# MainBoard_Eagle7.net
KiCad netlist of a schematic drawn in EAGLE
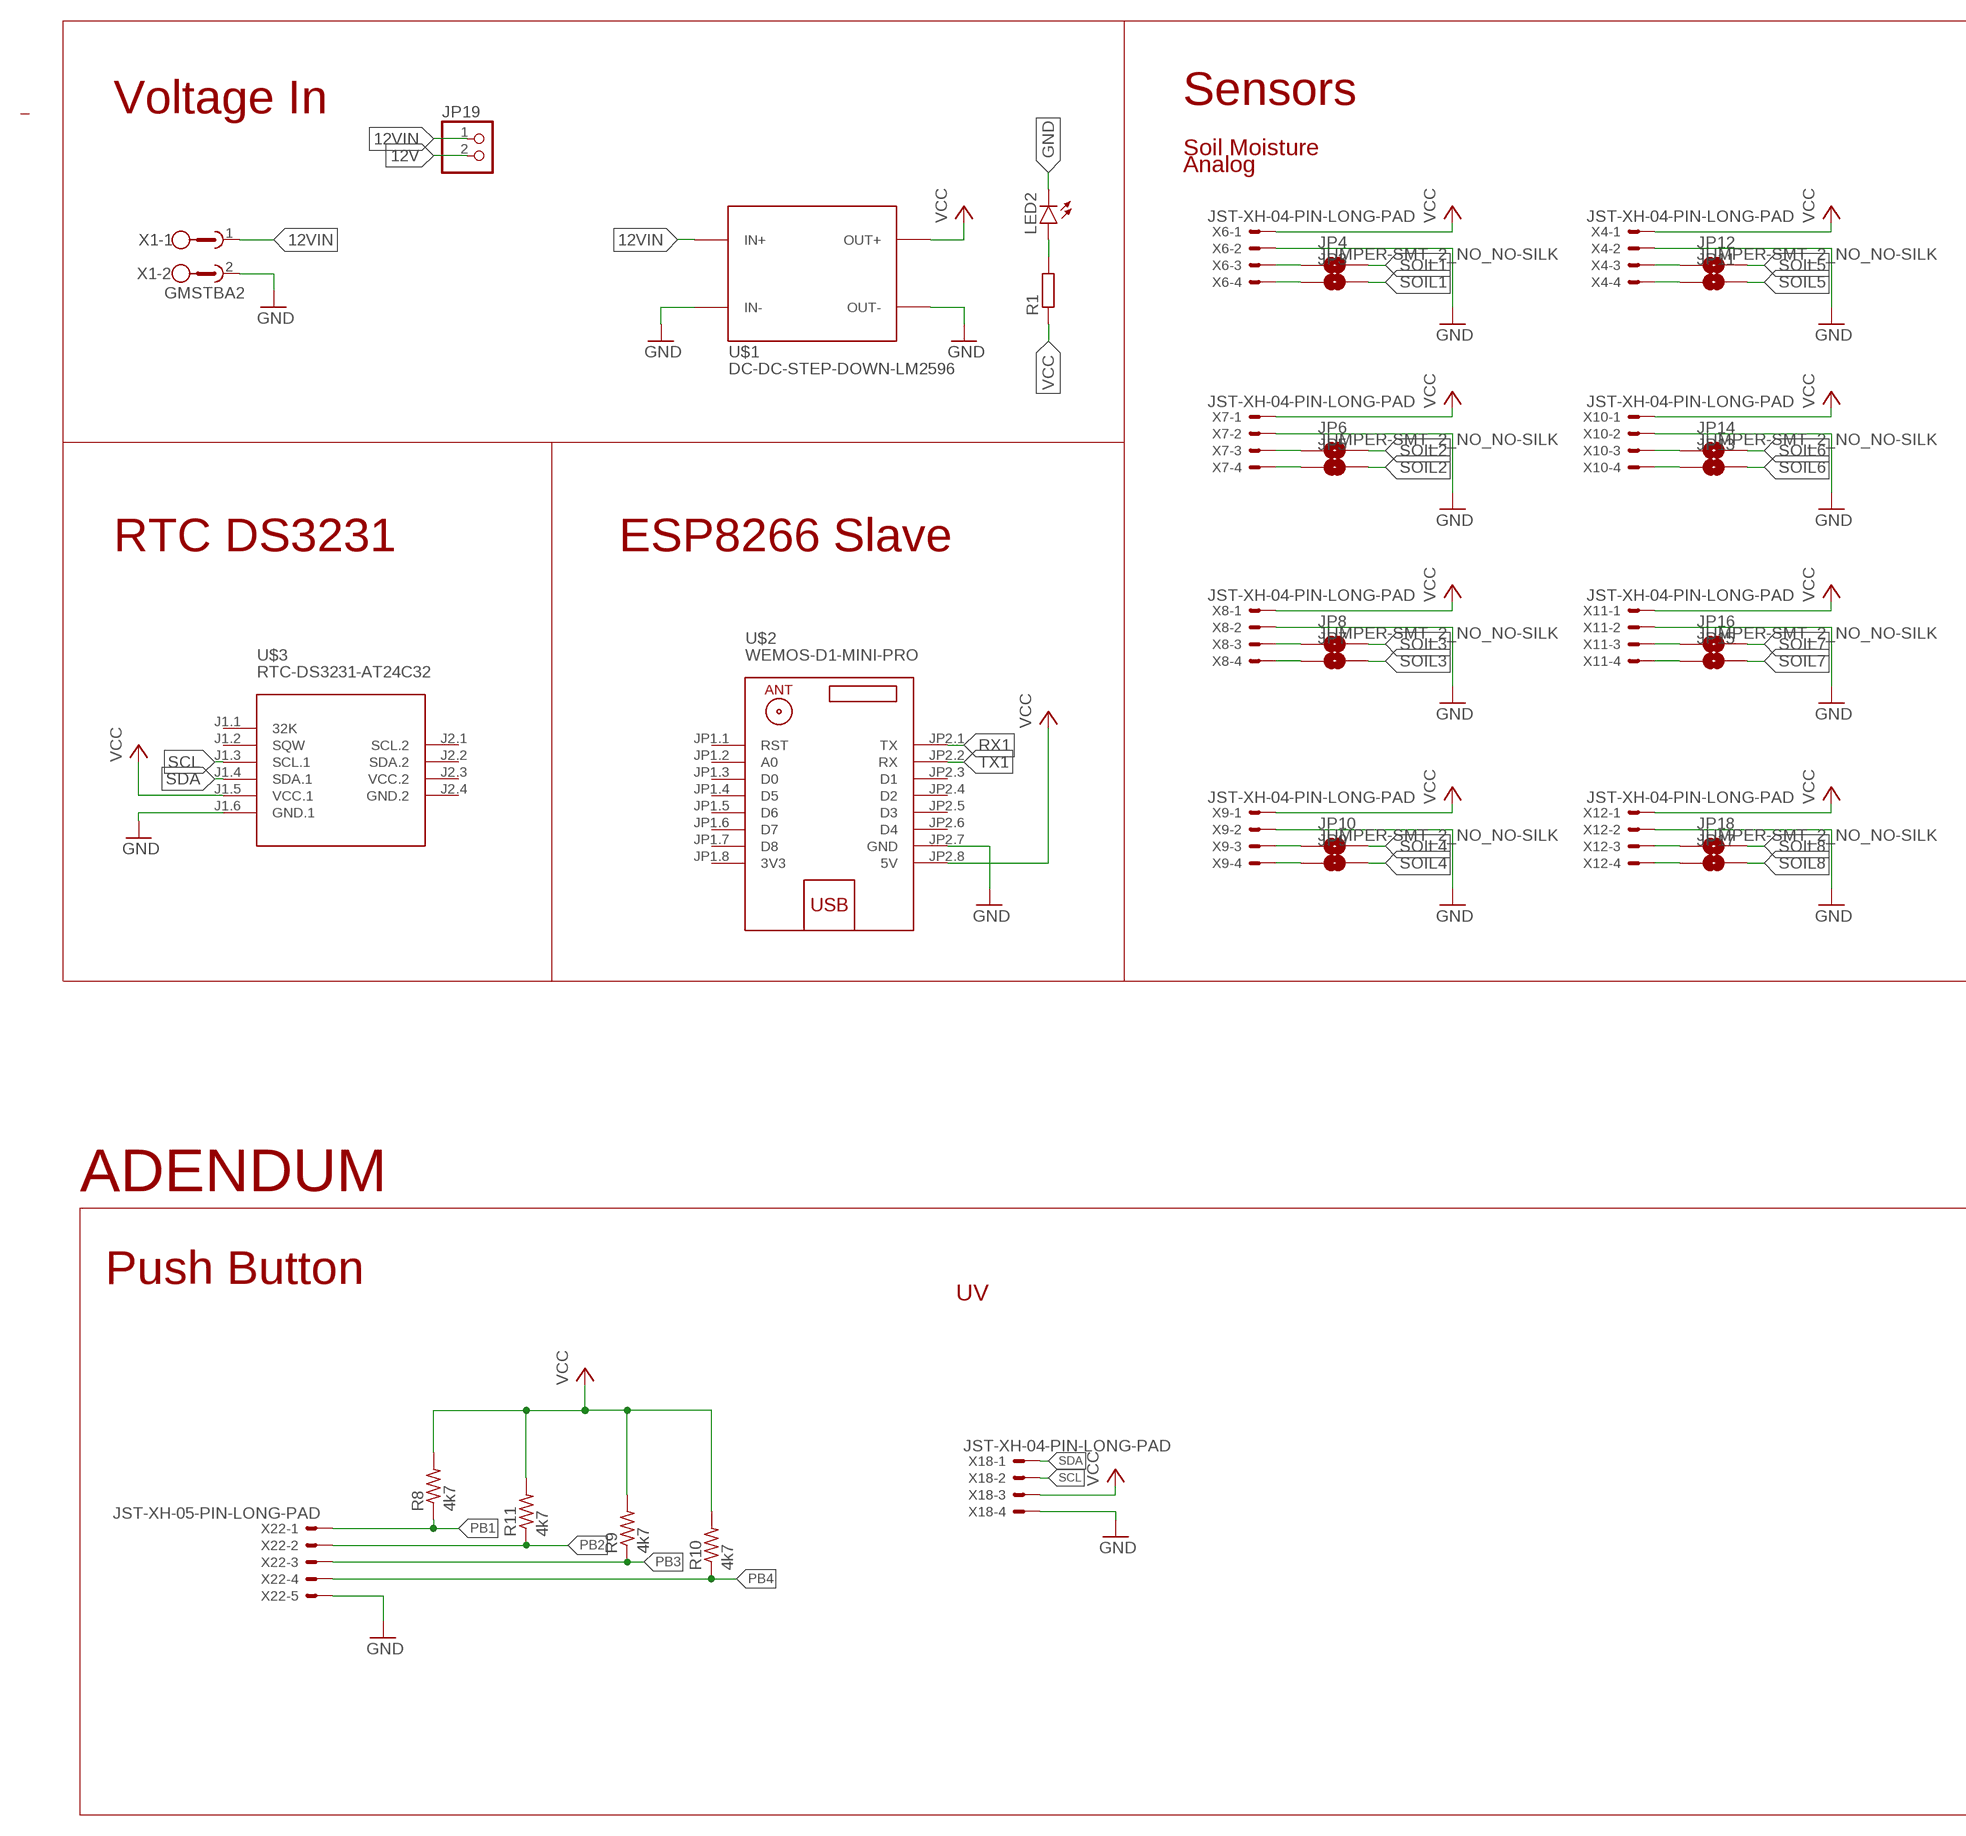
[diagram p0: schematic, sheet 1, part 1 of 2]
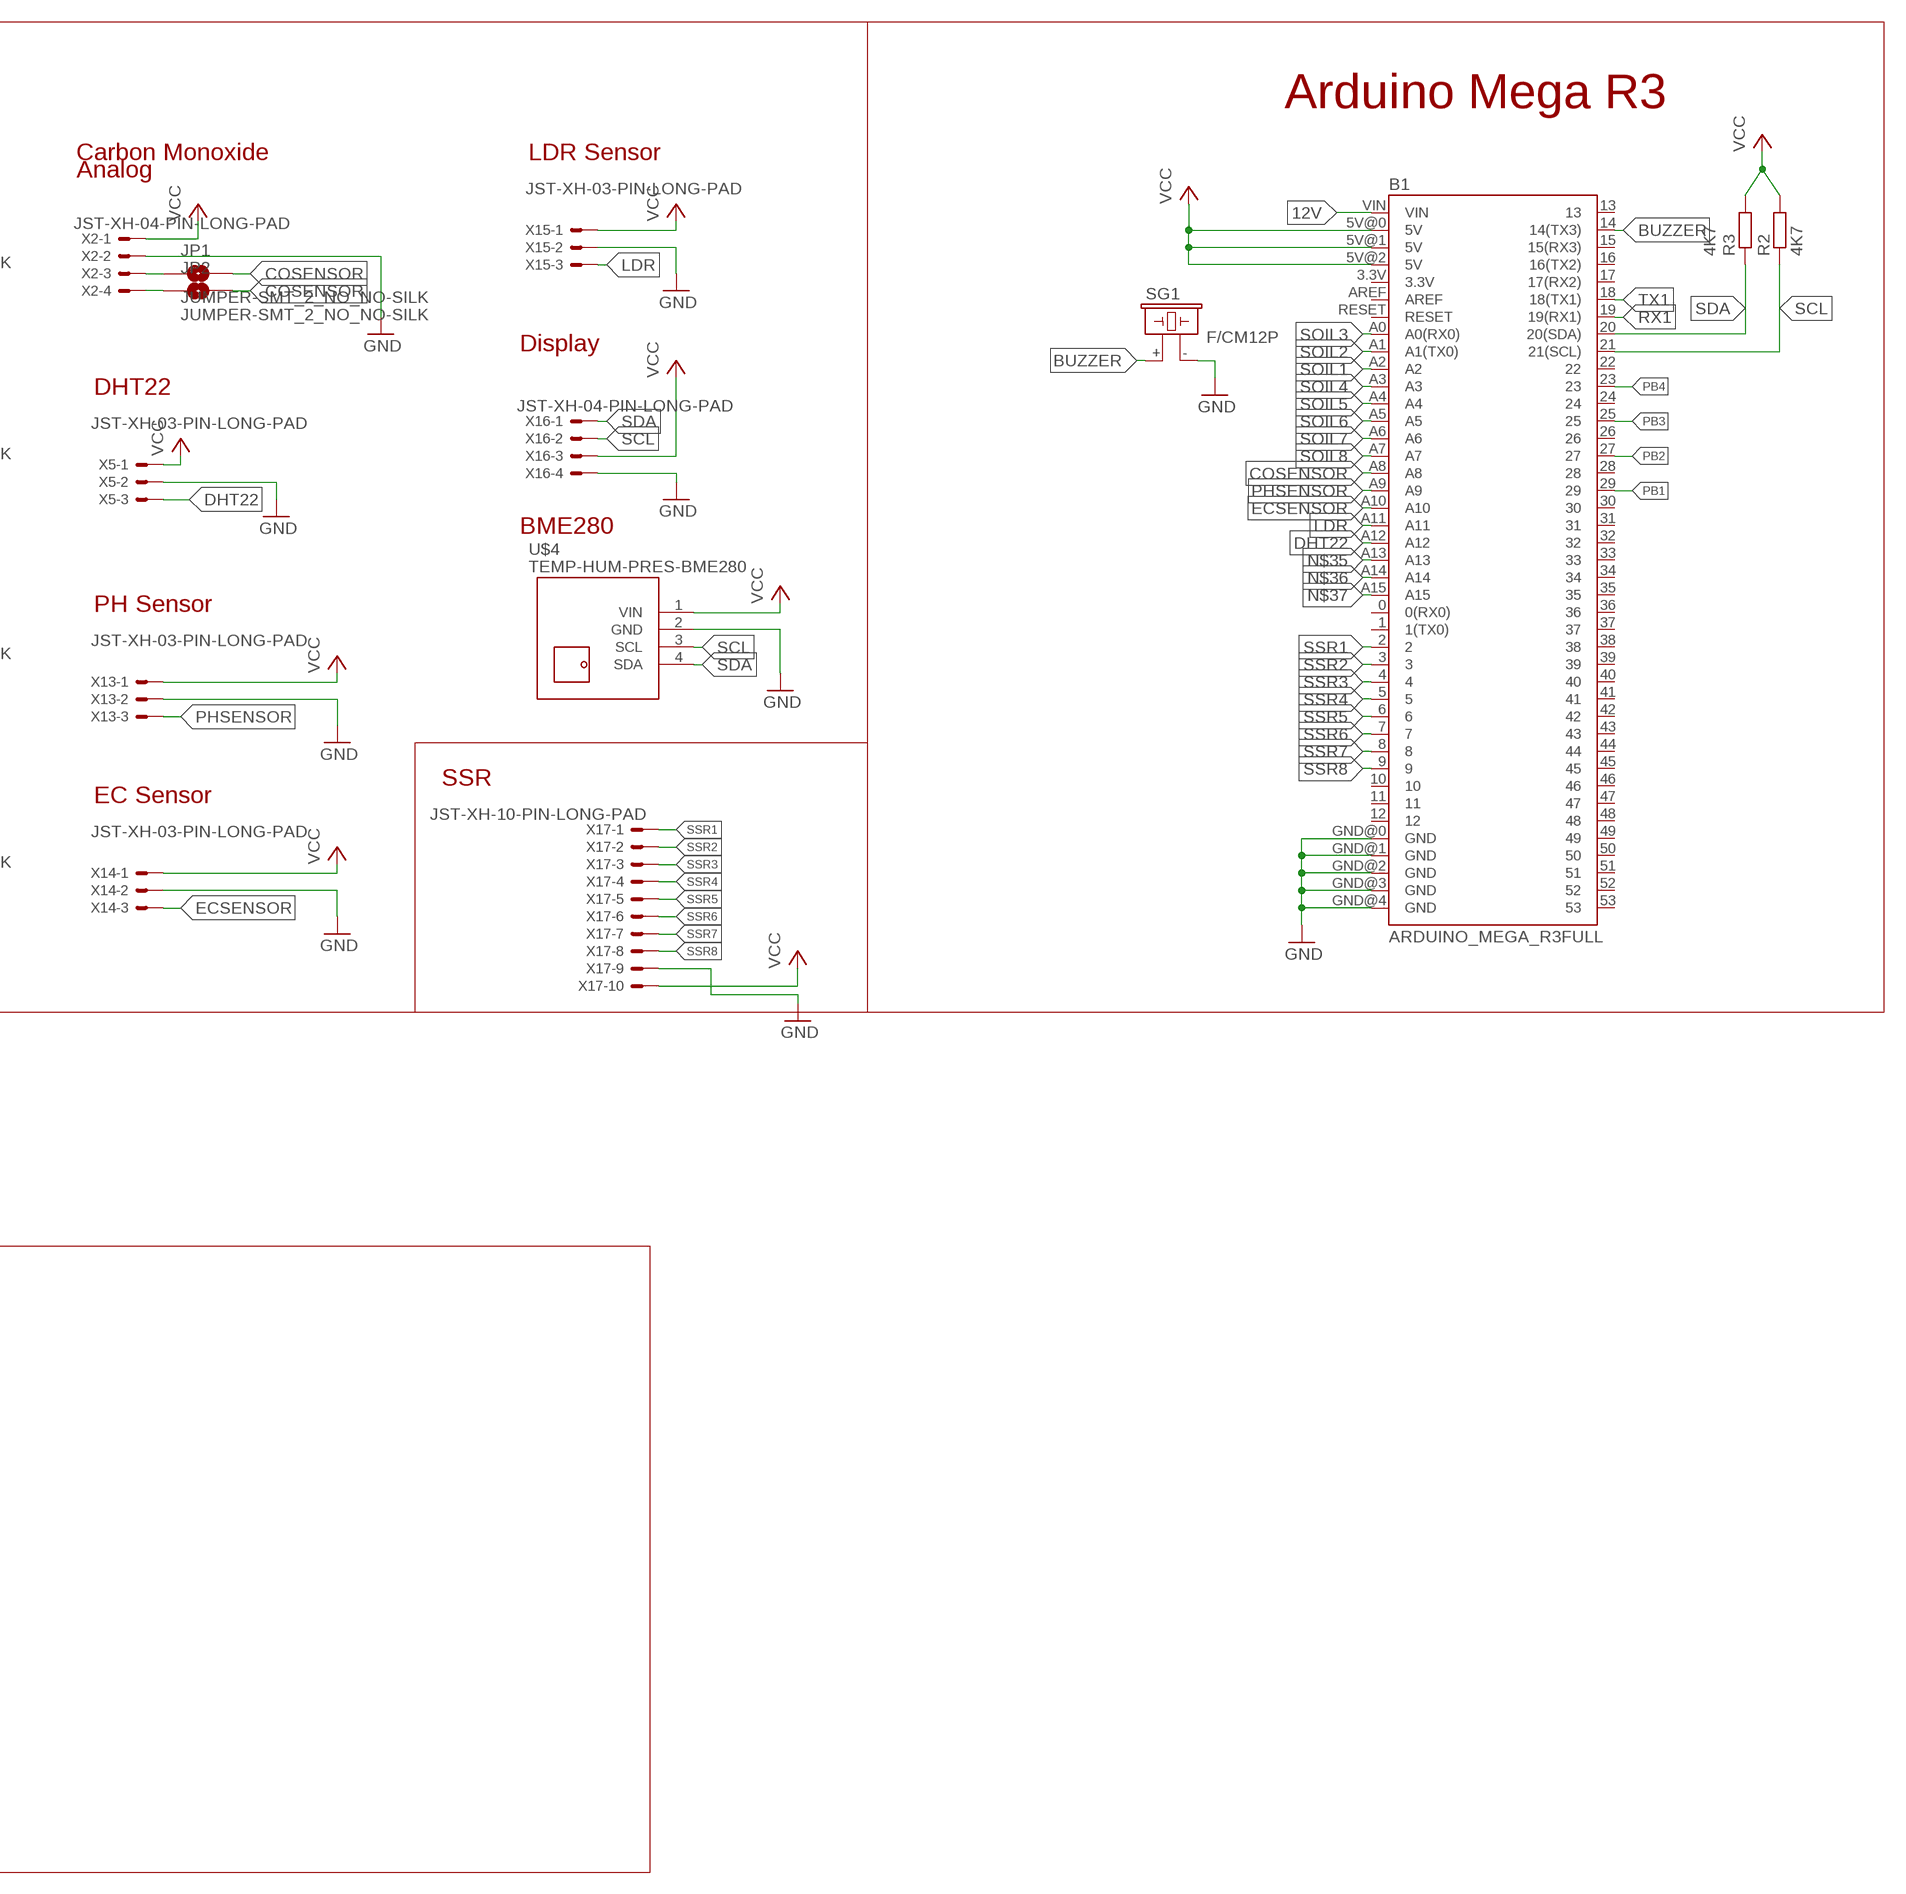
[diagram p1: schematic, sheet 1, part 2 of 2]

(export (version "E")
  (design (tool "Eeschema 10.0.6"))
  (components
    (comp (ref "B1")
      (value "ARDUINO_MEGA_R3FULL")
      (footprint "eagle-import:ARDUINO_MEGA")
      (libsource (lib "eagle-import") (part "ARDUINO_MEGA_R3FULL"))
    )
    (comp (ref "JP1")
      (value "JUMPER-SMT_2_NO_NO-SILK")
      (footprint "eagle-import:SMT-JUMPER_2_NO_NO-SILK")
      (libsource (lib "eagle-import") (part "JUMPER-SMT_2_NO_NO-SILK"))
    )
    (comp (ref "JP2")
      (value "JUMPER-SMT_2_NO_NO-SILK")
      (footprint "eagle-import:SMT-JUMPER_2_NO_NO-SILK")
      (libsource (lib "eagle-import") (part "JUMPER-SMT_2_NO_NO-SILK"))
    )
    (comp (ref "JP3")
      (value "JUMPER-SMT_2_NO_NO-SILK")
      (footprint "eagle-import:SMT-JUMPER_2_NO_NO-SILK")
      (libsource (lib "eagle-import") (part "JUMPER-SMT_2_NO_NO-SILK"))
    )
    (comp (ref "JP4")
      (value "JUMPER-SMT_2_NO_NO-SILK")
      (footprint "eagle-import:SMT-JUMPER_2_NO_NO-SILK")
      (libsource (lib "eagle-import") (part "JUMPER-SMT_2_NO_NO-SILK"))
    )
    (comp (ref "JP5")
      (value "JUMPER-SMT_2_NO_NO-SILK")
      (footprint "eagle-import:SMT-JUMPER_2_NO_NO-SILK")
      (libsource (lib "eagle-import") (part "JUMPER-SMT_2_NO_NO-SILK"))
    )
    (comp (ref "JP6")
      (value "JUMPER-SMT_2_NO_NO-SILK")
      (footprint "eagle-import:SMT-JUMPER_2_NO_NO-SILK")
      (libsource (lib "eagle-import") (part "JUMPER-SMT_2_NO_NO-SILK"))
    )
    (comp (ref "JP7")
      (value "JUMPER-SMT_2_NO_NO-SILK")
      (footprint "eagle-import:SMT-JUMPER_2_NO_NO-SILK")
      (libsource (lib "eagle-import") (part "JUMPER-SMT_2_NO_NO-SILK"))
    )
    (comp (ref "JP8")
      (value "JUMPER-SMT_2_NO_NO-SILK")
      (footprint "eagle-import:SMT-JUMPER_2_NO_NO-SILK")
      (libsource (lib "eagle-import") (part "JUMPER-SMT_2_NO_NO-SILK"))
    )
    (comp (ref "JP9")
      (value "JUMPER-SMT_2_NO_NO-SILK")
      (footprint "eagle-import:SMT-JUMPER_2_NO_NO-SILK")
      (libsource (lib "eagle-import") (part "JUMPER-SMT_2_NO_NO-SILK"))
    )
    (comp (ref "JP10")
      (value "JUMPER-SMT_2_NO_NO-SILK")
      (footprint "eagle-import:SMT-JUMPER_2_NO_NO-SILK")
      (libsource (lib "eagle-import") (part "JUMPER-SMT_2_NO_NO-SILK"))
    )
    (comp (ref "JP11")
      (value "JUMPER-SMT_2_NO_NO-SILK")
      (footprint "eagle-import:SMT-JUMPER_2_NO_NO-SILK")
      (libsource (lib "eagle-import") (part "JUMPER-SMT_2_NO_NO-SILK"))
    )
    (comp (ref "JP12")
      (value "JUMPER-SMT_2_NO_NO-SILK")
      (footprint "eagle-import:SMT-JUMPER_2_NO_NO-SILK")
      (libsource (lib "eagle-import") (part "JUMPER-SMT_2_NO_NO-SILK"))
    )
    (comp (ref "JP13")
      (value "JUMPER-SMT_2_NO_NO-SILK")
      (footprint "eagle-import:SMT-JUMPER_2_NO_NO-SILK")
      (libsource (lib "eagle-import") (part "JUMPER-SMT_2_NO_NO-SILK"))
    )
    (comp (ref "JP14")
      (value "JUMPER-SMT_2_NO_NO-SILK")
      (footprint "eagle-import:SMT-JUMPER_2_NO_NO-SILK")
      (libsource (lib "eagle-import") (part "JUMPER-SMT_2_NO_NO-SILK"))
    )
    (comp (ref "JP15")
      (value "JUMPER-SMT_2_NO_NO-SILK")
      (footprint "eagle-import:SMT-JUMPER_2_NO_NO-SILK")
      (libsource (lib "eagle-import") (part "JUMPER-SMT_2_NO_NO-SILK"))
    )
    (comp (ref "JP16")
      (value "JUMPER-SMT_2_NO_NO-SILK")
      (footprint "eagle-import:SMT-JUMPER_2_NO_NO-SILK")
      (libsource (lib "eagle-import") (part "JUMPER-SMT_2_NO_NO-SILK"))
    )
    (comp (ref "JP17")
      (value "JUMPER-SMT_2_NO_NO-SILK")
      (footprint "eagle-import:SMT-JUMPER_2_NO_NO-SILK")
      (libsource (lib "eagle-import") (part "JUMPER-SMT_2_NO_NO-SILK"))
    )
    (comp (ref "JP18")
      (value "JUMPER-SMT_2_NO_NO-SILK")
      (footprint "eagle-import:SMT-JUMPER_2_NO_NO-SILK")
      (libsource (lib "eagle-import") (part "JUMPER-SMT_2_NO_NO-SILK"))
    )
    (comp (ref "JP19")
      (value "PINHD-1X2")
      (footprint "eagle-import:1X02")
      (libsource (lib "eagle-import") (part "PINHD-1X2"))
    )
    (comp (ref "LED2")
      (value "LED5MM")
      (footprint "eagle-import:LED5MM")
      (libsource (lib "eagle-import") (part "LED5MM"))
    )
    (comp (ref "R1")
      (value "R-EU_R0805")
      (footprint "eagle-import:R0805")
      (libsource (lib "eagle-import") (part "R-EU_R0805"))
    )
    (comp (ref "R2")
      (value "4K7")
      (footprint "eagle-import:M0805")
      (libsource (lib "eagle-import") (part "rcl@1_R-EU_M0805"))
    )
    (comp (ref "R3")
      (value "4K7")
      (footprint "eagle-import:M0805")
      (libsource (lib "eagle-import") (part "rcl@1_R-EU_M0805"))
    )
    (comp (ref "R8")
      (value "4k7")
      (footprint "eagle-import:M0805")
      (libsource (lib "eagle-import") (part "R-US_M0805"))
    )
    (comp (ref "R9")
      (value "4k7")
      (footprint "eagle-import:M0805")
      (libsource (lib "eagle-import") (part "R-US_M0805"))
    )
    (comp (ref "R10")
      (value "4k7")
      (footprint "eagle-import:M0805")
      (libsource (lib "eagle-import") (part "R-US_M0805"))
    )
    (comp (ref "R11")
      (value "4k7")
      (footprint "eagle-import:M0805")
      (libsource (lib "eagle-import") (part "R-US_M0805"))
    )
    (comp (ref "SG1")
      (value "F/CM12P")
      (footprint "eagle-import:F_CM12P")
      (libsource (lib "eagle-import") (part "F/CM12P"))
    )
    (comp (ref "U$1")
      (value "DC-DC-STEP-DOWN-LM2596")
      (footprint "eagle-import:DC-DC-STEP-DOWN-LM2596")
      (libsource (lib "eagle-import") (part "DC-DC-STEP-DOWN-LM2596"))
    )
    (comp (ref "U$2")
      (value "WEMOS-D1-MINI-PRO")
      (footprint "eagle-import:WEMOS-D1-MINI-PRO")
      (libsource (lib "eagle-import") (part "WEMOS-D1-MINI-PRO"))
    )
    (comp (ref "U$3")
      (value "RTC-DS3231-AT24C32")
      (footprint "eagle-import:RTC-DS3231-AT24C32")
      (libsource (lib "eagle-import") (part "RTC-DS3231-AT24C32"))
    )
    (comp (ref "U$4")
      (value "TEMP-HUM-PRES-BME280")
      (footprint "eagle-import:TEMP-HUM-PRES-BME280")
      (libsource (lib "eagle-import") (part "TEMP-HUM-PRES-BME280"))
    )
    (comp (ref "X1")
      (value "GMSTBA2")
      (footprint "eagle-import:GMSTBA2")
      (fields (field (name "MF") "FARNELL") (field (name "MPN") "1757242"))
      (libsource (lib "eagle-import") (part "GMSTBA2"))
    )
    (comp (ref "X2")
      (value "JST-XH-04-PIN-LONG-PAD")
      (footprint "eagle-import:JST-XH-04-PACKAGE-LONG-PAD")
      (libsource (lib "eagle-import") (part "JST-XH-04-PIN-LONG-PAD"))
    )
    (comp (ref "X4")
      (value "JST-XH-04-PIN-LONG-PAD")
      (footprint "eagle-import:JST-XH-04-PACKAGE-LONG-PAD")
      (libsource (lib "eagle-import") (part "JST-XH-04-PIN-LONG-PAD"))
    )
    (comp (ref "X5")
      (value "JST-XH-03-PIN-LONG-PAD")
      (footprint "eagle-import:JST-XH-03-PACKAGE-LONG-PAD")
      (libsource (lib "eagle-import") (part "JST-XH-03-PIN-LONG-PAD"))
    )
    (comp (ref "X6")
      (value "JST-XH-04-PIN-LONG-PAD")
      (footprint "eagle-import:JST-XH-04-PACKAGE-LONG-PAD")
      (libsource (lib "eagle-import") (part "JST-XH-04-PIN-LONG-PAD"))
    )
    (comp (ref "X7")
      (value "JST-XH-04-PIN-LONG-PAD")
      (footprint "eagle-import:JST-XH-04-PACKAGE-LONG-PAD")
      (libsource (lib "eagle-import") (part "JST-XH-04-PIN-LONG-PAD"))
    )
    (comp (ref "X8")
      (value "JST-XH-04-PIN-LONG-PAD")
      (footprint "eagle-import:JST-XH-04-PACKAGE-LONG-PAD")
      (libsource (lib "eagle-import") (part "JST-XH-04-PIN-LONG-PAD"))
    )
    (comp (ref "X9")
      (value "JST-XH-04-PIN-LONG-PAD")
      (footprint "eagle-import:JST-XH-04-PACKAGE-LONG-PAD")
      (libsource (lib "eagle-import") (part "JST-XH-04-PIN-LONG-PAD"))
    )
    (comp (ref "X10")
      (value "JST-XH-04-PIN-LONG-PAD")
      (footprint "eagle-import:JST-XH-04-PACKAGE-LONG-PAD")
      (libsource (lib "eagle-import") (part "JST-XH-04-PIN-LONG-PAD"))
    )
    (comp (ref "X11")
      (value "JST-XH-04-PIN-LONG-PAD")
      (footprint "eagle-import:JST-XH-04-PACKAGE-LONG-PAD")
      (libsource (lib "eagle-import") (part "JST-XH-04-PIN-LONG-PAD"))
    )
    (comp (ref "X12")
      (value "JST-XH-04-PIN-LONG-PAD")
      (footprint "eagle-import:JST-XH-04-PACKAGE-LONG-PAD")
      (libsource (lib "eagle-import") (part "JST-XH-04-PIN-LONG-PAD"))
    )
    (comp (ref "X13")
      (value "JST-XH-03-PIN-LONG-PAD")
      (footprint "eagle-import:JST-XH-03-PACKAGE-LONG-PAD")
      (libsource (lib "eagle-import") (part "JST-XH-03-PIN-LONG-PAD"))
    )
    (comp (ref "X14")
      (value "JST-XH-03-PIN-LONG-PAD")
      (footprint "eagle-import:JST-XH-03-PACKAGE-LONG-PAD")
      (libsource (lib "eagle-import") (part "JST-XH-03-PIN-LONG-PAD"))
    )
    (comp (ref "X15")
      (value "JST-XH-03-PIN-LONG-PAD")
      (footprint "eagle-import:JST-XH-03-PACKAGE-LONG-PAD")
      (libsource (lib "eagle-import") (part "JST-XH-03-PIN-LONG-PAD"))
    )
    (comp (ref "X16")
      (value "JST-XH-04-PIN-LONG-PAD")
      (footprint "eagle-import:JST-XH-04-PACKAGE-LONG-PAD")
      (libsource (lib "eagle-import") (part "JST-XH-04-PIN-LONG-PAD"))
    )
    (comp (ref "X17")
      (value "JST-XH-10-PIN-LONG-PAD")
      (footprint "eagle-import:JST-XH-10-PACKAGE-LONG-PAD")
      (libsource (lib "eagle-import") (part "JST-XH-10-PIN-LONG-PAD"))
    )
    (comp (ref "X18")
      (value "JST-XH-04-PIN-LONG-PAD")
      (footprint "eagle-import:JST-XH-04-PACKAGE-LONG-PAD")
      (libsource (lib "eagle-import") (part "JST-XH-04-PIN-LONG-PAD"))
    )
    (comp (ref "X22")
      (value "JST-XH-05-PIN-LONG-PAD")
      (footprint "eagle-import:JST-XH-05-PACKAGE-LONG-PAD")
      (libsource (lib "eagle-import") (part "JST-XH-05-PIN-LONG-PAD"))
    )
  )
  (nets
    (net (code "1") (name "/3V3") (class "Default")
      (node (ref "U$2") (pin "JP1.8") (pinfunction "3V3_JP1.8") (pintype "power_in"))
    )
    (net (code "2") (name "/GND.2") (class "Default")
      (node (ref "U$3") (pin "J2.4") (pinfunction "GND.2_J2.4") (pintype "power_in"))
    )
    (net (code "3") (name "/VCC.2") (class "Default")
      (node (ref "U$3") (pin "J2.3") (pinfunction "VCC.2_J2.3") (pintype "power_in"))
    )
    (net (code "4") (name "12V") (class "Default")
      (node (ref "B1") (pin "VIN") (pinfunction "VIN_VIN") (pintype "bidirectional"))
      (node (ref "JP19") (pin "2") (pinfunction "2_2") (pintype "passive"))
    )
    (net (code "5") (name "12VIN") (class "Default")
      (node (ref "JP19") (pin "1") (pinfunction "1_1") (pintype "passive"))
      (node (ref "U$1") (pin "IN+") (pinfunction "IN+_IN+") (pintype "bidirectional"))
      (node (ref "X1") (pin "1") (pinfunction "1_1") (pintype "passive"))
    )
    (net (code "6") (name "BUZZER") (class "Default")
      (node (ref "B1") (pin "14") (pinfunction "14(TX3)_14") (pintype "bidirectional"))
      (node (ref "SG1") (pin "+") (pinfunction "1_+") (pintype "passive"))
    )
    (net (code "7") (name "COSENSOR") (class "Default")
      (node (ref "B1") (pin "A8") (pinfunction "A8_A8") (pintype "bidirectional"))
      (node (ref "JP1") (pin "2") (pinfunction "2_2") (pintype "passive"))
      (node (ref "JP2") (pin "2") (pinfunction "2_2") (pintype "passive"))
    )
    (net (code "8") (name "DHT22") (class "Default")
      (node (ref "B1") (pin "A12") (pinfunction "A12_A12") (pintype "bidirectional"))
      (node (ref "X5") (pin "3") (pinfunction "S_3") (pintype "passive"))
    )
    (net (code "9") (name "ECSENSOR") (class "Default")
      (node (ref "B1") (pin "A10") (pinfunction "A10_A10") (pintype "bidirectional"))
      (node (ref "X14") (pin "3") (pinfunction "S_3") (pintype "passive"))
    )
    (net (code "10") (name "GND") (class "Default")
      (node (ref "B1") (pin "GND@0") (pinfunction "GND_GND@0") (pintype "bidirectional"))
      (node (ref "B1") (pin "GND@1") (pinfunction "GND_GND@1") (pintype "bidirectional"))
      (node (ref "B1") (pin "GND@2") (pinfunction "GND_GND@2") (pintype "bidirectional"))
      (node (ref "B1") (pin "GND@3") (pinfunction "GND_GND@3") (pintype "bidirectional"))
      (node (ref "B1") (pin "GND@4") (pinfunction "GND_GND@4") (pintype "bidirectional"))
      (node (ref "LED2") (pin "K") (pinfunction "C_K") (pintype "passive"))
      (node (ref "SG1") (pin "-") (pinfunction "2_-") (pintype "passive"))
      (node (ref "U$1") (pin "IN-") (pinfunction "IN-_IN-") (pintype "bidirectional"))
      (node (ref "U$1") (pin "OUT-") (pinfunction "OUT-_OUT-") (pintype "bidirectional"))
      (node (ref "U$2") (pin "JP2.7") (pinfunction "GND_JP2.7") (pintype "power_in"))
      (node (ref "U$3") (pin "J1.6") (pinfunction "GND.1_J1.6") (pintype "power_in"))
      (node (ref "U$4") (pin "2") (pinfunction "GND_2") (pintype "power_in"))
      (node (ref "X1") (pin "2") (pinfunction "1_2") (pintype "passive"))
      (node (ref "X10") (pin "2") (pinfunction "S_2") (pintype "passive"))
      (node (ref "X11") (pin "2") (pinfunction "S_2") (pintype "passive"))
      (node (ref "X12") (pin "2") (pinfunction "S_2") (pintype "passive"))
      (node (ref "X13") (pin "2") (pinfunction "S_2") (pintype "passive"))
      (node (ref "X14") (pin "2") (pinfunction "S_2") (pintype "passive"))
      (node (ref "X15") (pin "2") (pinfunction "S_2") (pintype "passive"))
      (node (ref "X16") (pin "4") (pinfunction "S_4") (pintype "passive"))
      (node (ref "X17") (pin "9") (pinfunction "S_9") (pintype "passive"))
      (node (ref "X18") (pin "4") (pinfunction "S_4") (pintype "passive"))
      (node (ref "X2") (pin "2") (pinfunction "S_2") (pintype "passive"))
      (node (ref "X22") (pin "5") (pinfunction "S_5") (pintype "passive"))
      (node (ref "X4") (pin "2") (pinfunction "S_2") (pintype "passive"))
      (node (ref "X5") (pin "2") (pinfunction "S_2") (pintype "passive"))
      (node (ref "X6") (pin "2") (pinfunction "S_2") (pintype "passive"))
      (node (ref "X7") (pin "2") (pinfunction "S_2") (pintype "passive"))
      (node (ref "X8") (pin "2") (pinfunction "S_2") (pintype "passive"))
      (node (ref "X9") (pin "2") (pinfunction "S_2") (pintype "passive"))
    )
    (net (code "11") (name "LDR") (class "Default")
      (node (ref "B1") (pin "A11") (pinfunction "A11_A11") (pintype "bidirectional"))
      (node (ref "X15") (pin "3") (pinfunction "S_3") (pintype "passive"))
    )
    (net (code "12") (name "N$35") (class "Default")
      (node (ref "B1") (pin "A13") (pinfunction "A13_A13") (pintype "bidirectional"))
    )
    (net (code "13") (name "N$36") (class "Default")
      (node (ref "B1") (pin "A14") (pinfunction "A14_A14") (pintype "bidirectional"))
    )
    (net (code "14") (name "N$37") (class "Default")
      (node (ref "B1") (pin "A15") (pinfunction "A15_A15") (pintype "bidirectional"))
    )
    (net (code "15") (name "Net-(LED2-PadA)") (class "Default")
      (node (ref "LED2") (pin "A") (pinfunction "A_A") (pintype "passive"))
      (node (ref "R1") (pin "2") (pinfunction "2_2") (pintype "passive"))
    )
    (net (code "16") (name "Net-(X2C-S)") (class "Default")
      (node (ref "JP1") (pin "1") (pinfunction "1_1") (pintype "passive"))
      (node (ref "X2") (pin "3") (pinfunction "S_3") (pintype "passive"))
    )
    (net (code "17") (name "Net-(X2D-S)") (class "Default")
      (node (ref "JP2") (pin "1") (pinfunction "1_1") (pintype "passive"))
      (node (ref "X2") (pin "4") (pinfunction "S_4") (pintype "passive"))
    )
    (net (code "18") (name "Net-(X4C-S)") (class "Default")
      (node (ref "JP12") (pin "1") (pinfunction "1_1") (pintype "passive"))
      (node (ref "X4") (pin "3") (pinfunction "S_3") (pintype "passive"))
    )
    (net (code "19") (name "Net-(X4D-S)") (class "Default")
      (node (ref "JP11") (pin "1") (pinfunction "1_1") (pintype "passive"))
      (node (ref "X4") (pin "4") (pinfunction "S_4") (pintype "passive"))
    )
    (net (code "20") (name "Net-(X6C-S)") (class "Default")
      (node (ref "JP4") (pin "1") (pinfunction "1_1") (pintype "passive"))
      (node (ref "X6") (pin "3") (pinfunction "S_3") (pintype "passive"))
    )
    (net (code "21") (name "Net-(X6D-S)") (class "Default")
      (node (ref "JP3") (pin "1") (pinfunction "1_1") (pintype "passive"))
      (node (ref "X6") (pin "4") (pinfunction "S_4") (pintype "passive"))
    )
    (net (code "22") (name "Net-(X7C-S)") (class "Default")
      (node (ref "JP6") (pin "1") (pinfunction "1_1") (pintype "passive"))
      (node (ref "X7") (pin "3") (pinfunction "S_3") (pintype "passive"))
    )
    (net (code "23") (name "Net-(X7D-S)") (class "Default")
      (node (ref "JP5") (pin "1") (pinfunction "1_1") (pintype "passive"))
      (node (ref "X7") (pin "4") (pinfunction "S_4") (pintype "passive"))
    )
    (net (code "24") (name "Net-(X8C-S)") (class "Default")
      (node (ref "JP8") (pin "1") (pinfunction "1_1") (pintype "passive"))
      (node (ref "X8") (pin "3") (pinfunction "S_3") (pintype "passive"))
    )
    (net (code "25") (name "Net-(X8D-S)") (class "Default")
      (node (ref "JP7") (pin "1") (pinfunction "1_1") (pintype "passive"))
      (node (ref "X8") (pin "4") (pinfunction "S_4") (pintype "passive"))
    )
    (net (code "26") (name "Net-(X9C-S)") (class "Default")
      (node (ref "JP10") (pin "1") (pinfunction "1_1") (pintype "passive"))
      (node (ref "X9") (pin "3") (pinfunction "S_3") (pintype "passive"))
    )
    (net (code "27") (name "Net-(X9D-S)") (class "Default")
      (node (ref "JP9") (pin "1") (pinfunction "1_1") (pintype "passive"))
      (node (ref "X9") (pin "4") (pinfunction "S_4") (pintype "passive"))
    )
    (net (code "28") (name "Net-(X10C-S)") (class "Default")
      (node (ref "JP14") (pin "1") (pinfunction "1_1") (pintype "passive"))
      (node (ref "X10") (pin "3") (pinfunction "S_3") (pintype "passive"))
    )
    (net (code "29") (name "Net-(X10D-S)") (class "Default")
      (node (ref "JP13") (pin "1") (pinfunction "1_1") (pintype "passive"))
      (node (ref "X10") (pin "4") (pinfunction "S_4") (pintype "passive"))
    )
    (net (code "30") (name "Net-(X11C-S)") (class "Default")
      (node (ref "JP16") (pin "1") (pinfunction "1_1") (pintype "passive"))
      (node (ref "X11") (pin "3") (pinfunction "S_3") (pintype "passive"))
    )
    (net (code "31") (name "Net-(X11D-S)") (class "Default")
      (node (ref "JP15") (pin "1") (pinfunction "1_1") (pintype "passive"))
      (node (ref "X11") (pin "4") (pinfunction "S_4") (pintype "passive"))
    )
    (net (code "32") (name "Net-(X12C-S)") (class "Default")
      (node (ref "JP18") (pin "1") (pinfunction "1_1") (pintype "passive"))
      (node (ref "X12") (pin "3") (pinfunction "S_3") (pintype "passive"))
    )
    (net (code "33") (name "Net-(X12D-S)") (class "Default")
      (node (ref "JP17") (pin "1") (pinfunction "1_1") (pintype "passive"))
      (node (ref "X12") (pin "4") (pinfunction "S_4") (pintype "passive"))
    )
    (net (code "34") (name "PB1") (class "Default")
      (node (ref "B1") (pin "29") (pinfunction "29_29") (pintype "bidirectional"))
      (node (ref "R8") (pin "1") (pinfunction "1_1") (pintype "passive"))
      (node (ref "X22") (pin "1") (pinfunction "S_1") (pintype "passive"))
    )
    (net (code "35") (name "PB2") (class "Default")
      (node (ref "B1") (pin "27") (pinfunction "27_27") (pintype "bidirectional"))
      (node (ref "R11") (pin "1") (pinfunction "1_1") (pintype "passive"))
      (node (ref "X22") (pin "2") (pinfunction "S_2") (pintype "passive"))
    )
    (net (code "36") (name "PB3") (class "Default")
      (node (ref "B1") (pin "25") (pinfunction "25_25") (pintype "bidirectional"))
      (node (ref "R9") (pin "1") (pinfunction "1_1") (pintype "passive"))
      (node (ref "X22") (pin "3") (pinfunction "S_3") (pintype "passive"))
    )
    (net (code "37") (name "PB4") (class "Default")
      (node (ref "B1") (pin "23") (pinfunction "23_23") (pintype "bidirectional"))
      (node (ref "R10") (pin "1") (pinfunction "1_1") (pintype "passive"))
      (node (ref "X22") (pin "4") (pinfunction "S_4") (pintype "passive"))
    )
    (net (code "38") (name "PHSENSOR") (class "Default")
      (node (ref "B1") (pin "A9") (pinfunction "A9_A9") (pintype "bidirectional"))
      (node (ref "X13") (pin "3") (pinfunction "S_3") (pintype "passive"))
    )
    (net (code "39") (name "RX1") (class "Default")
      (node (ref "B1") (pin "19") (pinfunction "19(RX1)_19") (pintype "bidirectional"))
      (node (ref "U$2") (pin "JP2.1") (pinfunction "TX_JP2.1") (pintype "bidirectional"))
    )
    (net (code "40") (name "SCL") (class "Default")
      (node (ref "B1") (pin "21") (pinfunction "21(SCL)_21") (pintype "bidirectional"))
      (node (ref "R2") (pin "1") (pinfunction "1_1") (pintype "passive"))
      (node (ref "U$3") (pin "J1.3") (pinfunction "SCL.1_J1.3") (pintype "bidirectional"))
      (node (ref "U$4") (pin "3") (pinfunction "SCL_3") (pintype "bidirectional"))
      (node (ref "X16") (pin "2") (pinfunction "S_2") (pintype "passive"))
      (node (ref "X18") (pin "2") (pinfunction "S_2") (pintype "passive"))
    )
    (net (code "41") (name "SDA") (class "Default")
      (node (ref "B1") (pin "20") (pinfunction "20(SDA)_20") (pintype "bidirectional"))
      (node (ref "R3") (pin "1") (pinfunction "1_1") (pintype "passive"))
      (node (ref "U$3") (pin "J1.4") (pinfunction "SDA.1_J1.4") (pintype "bidirectional"))
      (node (ref "U$4") (pin "4") (pinfunction "SDA_4") (pintype "bidirectional"))
      (node (ref "X16") (pin "1") (pinfunction "S_1") (pintype "passive"))
      (node (ref "X18") (pin "1") (pinfunction "S_1") (pintype "passive"))
    )
    (net (code "42") (name "SOIL1") (class "Default")
      (node (ref "B1") (pin "A2") (pinfunction "A2_A2") (pintype "bidirectional"))
      (node (ref "JP3") (pin "2") (pinfunction "2_2") (pintype "passive"))
      (node (ref "JP4") (pin "2") (pinfunction "2_2") (pintype "passive"))
    )
    (net (code "43") (name "SOIL2") (class "Default")
      (node (ref "B1") (pin "A1") (pinfunction "A1(TX0)_A1") (pintype "bidirectional"))
      (node (ref "JP5") (pin "2") (pinfunction "2_2") (pintype "passive"))
      (node (ref "JP6") (pin "2") (pinfunction "2_2") (pintype "passive"))
    )
    (net (code "44") (name "SOIL3") (class "Default")
      (node (ref "B1") (pin "A0") (pinfunction "A0(RX0)_A0") (pintype "bidirectional"))
      (node (ref "JP7") (pin "2") (pinfunction "2_2") (pintype "passive"))
      (node (ref "JP8") (pin "2") (pinfunction "2_2") (pintype "passive"))
    )
    (net (code "45") (name "SOIL4") (class "Default")
      (node (ref "B1") (pin "A3") (pinfunction "A3_A3") (pintype "bidirectional"))
      (node (ref "JP10") (pin "2") (pinfunction "2_2") (pintype "passive"))
      (node (ref "JP9") (pin "2") (pinfunction "2_2") (pintype "passive"))
    )
    (net (code "46") (name "SOIL5") (class "Default")
      (node (ref "B1") (pin "A4") (pinfunction "A4_A4") (pintype "bidirectional"))
      (node (ref "JP11") (pin "2") (pinfunction "2_2") (pintype "passive"))
      (node (ref "JP12") (pin "2") (pinfunction "2_2") (pintype "passive"))
    )
    (net (code "47") (name "SOIL6") (class "Default")
      (node (ref "B1") (pin "A5") (pinfunction "A5_A5") (pintype "bidirectional"))
      (node (ref "JP13") (pin "2") (pinfunction "2_2") (pintype "passive"))
      (node (ref "JP14") (pin "2") (pinfunction "2_2") (pintype "passive"))
    )
    (net (code "48") (name "SOIL7") (class "Default")
      (node (ref "B1") (pin "A6") (pinfunction "A6_A6") (pintype "bidirectional"))
      (node (ref "JP15") (pin "2") (pinfunction "2_2") (pintype "passive"))
      (node (ref "JP16") (pin "2") (pinfunction "2_2") (pintype "passive"))
    )
    (net (code "49") (name "SOIL8") (class "Default")
      (node (ref "B1") (pin "A7") (pinfunction "A7_A7") (pintype "bidirectional"))
      (node (ref "JP17") (pin "2") (pinfunction "2_2") (pintype "passive"))
      (node (ref "JP18") (pin "2") (pinfunction "2_2") (pintype "passive"))
    )
    (net (code "50") (name "SSR1") (class "Default")
      (node (ref "B1") (pin "2") (pinfunction "2_2") (pintype "bidirectional"))
      (node (ref "X17") (pin "1") (pinfunction "S_1") (pintype "passive"))
    )
    (net (code "51") (name "SSR2") (class "Default")
      (node (ref "B1") (pin "3") (pinfunction "3_3") (pintype "bidirectional"))
      (node (ref "X17") (pin "2") (pinfunction "S_2") (pintype "passive"))
    )
    (net (code "52") (name "SSR3") (class "Default")
      (node (ref "B1") (pin "4") (pinfunction "4_4") (pintype "bidirectional"))
      (node (ref "X17") (pin "3") (pinfunction "S_3") (pintype "passive"))
    )
    (net (code "53") (name "SSR4") (class "Default")
      (node (ref "B1") (pin "5") (pinfunction "5_5") (pintype "bidirectional"))
      (node (ref "X17") (pin "4") (pinfunction "S_4") (pintype "passive"))
    )
    (net (code "54") (name "SSR5") (class "Default")
      (node (ref "B1") (pin "6") (pinfunction "6_6") (pintype "bidirectional"))
      (node (ref "X17") (pin "5") (pinfunction "S_5") (pintype "passive"))
    )
    (net (code "55") (name "SSR6") (class "Default")
      (node (ref "B1") (pin "7") (pinfunction "7_7") (pintype "bidirectional"))
      (node (ref "X17") (pin "6") (pinfunction "S_6") (pintype "passive"))
    )
    (net (code "56") (name "SSR7") (class "Default")
      (node (ref "B1") (pin "8") (pinfunction "8_8") (pintype "bidirectional"))
      (node (ref "X17") (pin "7") (pinfunction "S_7") (pintype "passive"))
    )
    (net (code "57") (name "SSR8") (class "Default")
      (node (ref "B1") (pin "9") (pinfunction "9_9") (pintype "bidirectional"))
      (node (ref "X17") (pin "8") (pinfunction "S_8") (pintype "passive"))
    )
    (net (code "58") (name "TX1") (class "Default")
      (node (ref "B1") (pin "18") (pinfunction "18(TX1)_18") (pintype "bidirectional"))
      (node (ref "U$2") (pin "JP2.2") (pinfunction "RX_JP2.2") (pintype "bidirectional"))
    )
    (net (code "59") (name "VCC") (class "Default")
      (node (ref "B1") (pin "5V@0") (pinfunction "5V_5V@0") (pintype "bidirectional"))
      (node (ref "B1") (pin "5V@1") (pinfunction "5V_5V@1") (pintype "bidirectional"))
      (node (ref "B1") (pin "5V@2") (pinfunction "5V_5V@2") (pintype "bidirectional"))
      (node (ref "R1") (pin "1") (pinfunction "1_1") (pintype "passive"))
      (node (ref "R10") (pin "2") (pinfunction "2_2") (pintype "passive"))
      (node (ref "R11") (pin "2") (pinfunction "2_2") (pintype "passive"))
      (node (ref "R2") (pin "2") (pinfunction "2_2") (pintype "passive"))
      (node (ref "R3") (pin "2") (pinfunction "2_2") (pintype "passive"))
      (node (ref "R8") (pin "2") (pinfunction "2_2") (pintype "passive"))
      (node (ref "R9") (pin "2") (pinfunction "2_2") (pintype "passive"))
      (node (ref "U$1") (pin "OUT+") (pinfunction "OUT+_OUT+") (pintype "bidirectional"))
      (node (ref "U$2") (pin "JP2.8") (pinfunction "5V_JP2.8") (pintype "power_in"))
      (node (ref "U$3") (pin "J1.5") (pinfunction "VCC.1_J1.5") (pintype "power_in"))
      (node (ref "U$4") (pin "1") (pinfunction "VIN_1") (pintype "power_in"))
      (node (ref "X10") (pin "1") (pinfunction "S_1") (pintype "passive"))
      (node (ref "X11") (pin "1") (pinfunction "S_1") (pintype "passive"))
      (node (ref "X12") (pin "1") (pinfunction "S_1") (pintype "passive"))
      (node (ref "X13") (pin "1") (pinfunction "S_1") (pintype "passive"))
      (node (ref "X14") (pin "1") (pinfunction "S_1") (pintype "passive"))
      (node (ref "X15") (pin "1") (pinfunction "S_1") (pintype "passive"))
      (node (ref "X16") (pin "3") (pinfunction "S_3") (pintype "passive"))
      (node (ref "X17") (pin "10") (pinfunction "S_10") (pintype "passive"))
      (node (ref "X18") (pin "3") (pinfunction "S_3") (pintype "passive"))
      (node (ref "X2") (pin "1") (pinfunction "S_1") (pintype "passive"))
      (node (ref "X4") (pin "1") (pinfunction "S_1") (pintype "passive"))
      (node (ref "X5") (pin "1") (pinfunction "S_1") (pintype "passive"))
      (node (ref "X6") (pin "1") (pinfunction "S_1") (pintype "passive"))
      (node (ref "X7") (pin "1") (pinfunction "S_1") (pintype "passive"))
      (node (ref "X8") (pin "1") (pinfunction "S_1") (pintype "passive"))
      (node (ref "X9") (pin "1") (pinfunction "S_1") (pintype "passive"))
    )
    (net (code "60") (name "unconnected-(B1-0(RX0)-Pad0)") (class "Default")
      (node (ref "B1") (pin "0") (pinfunction "0(RX0)_0") (pintype "bidirectional"))
    )
    (net (code "61") (name "unconnected-(B1-1(TX0)-Pad1)") (class "Default")
      (node (ref "B1") (pin "1") (pinfunction "1(TX0)_1") (pintype "bidirectional"))
    )
    (net (code "62") (name "unconnected-(B1-15(RX3)-Pad15)") (class "Default")
      (node (ref "B1") (pin "15") (pinfunction "15(RX3)_15") (pintype "bidirectional"))
    )
    (net (code "63") (name "unconnected-(B1-16(TX2)-Pad16)") (class "Default")
      (node (ref "B1") (pin "16") (pinfunction "16(TX2)_16") (pintype "bidirectional"))
    )
    (net (code "64") (name "unconnected-(B1-17(RX2)-Pad17)") (class "Default")
      (node (ref "B1") (pin "17") (pinfunction "17(RX2)_17") (pintype "bidirectional"))
    )
    (net (code "65") (name "unconnected-(B1-Pad3.3V)") (class "Default")
      (node (ref "B1") (pin "3.3V") (pinfunction "3.3V_3.3V") (pintype "bidirectional"))
    )
    (net (code "66") (name "unconnected-(B1-Pad10)") (class "Default")
      (node (ref "B1") (pin "10") (pinfunction "10_10") (pintype "bidirectional"))
    )
    (net (code "67") (name "unconnected-(B1-Pad11)") (class "Default")
      (node (ref "B1") (pin "11") (pinfunction "11_11") (pintype "bidirectional"))
    )
    (net (code "68") (name "unconnected-(B1-Pad12)") (class "Default")
      (node (ref "B1") (pin "12") (pinfunction "12_12") (pintype "bidirectional"))
    )
    (net (code "69") (name "unconnected-(B1-Pad13)") (class "Default")
      (node (ref "B1") (pin "13") (pinfunction "13_13") (pintype "bidirectional"))
    )
    (net (code "70") (name "unconnected-(B1-Pad22)") (class "Default")
      (node (ref "B1") (pin "22") (pinfunction "22_22") (pintype "bidirectional"))
    )
    (net (code "71") (name "unconnected-(B1-Pad24)") (class "Default")
      (node (ref "B1") (pin "24") (pinfunction "24_24") (pintype "bidirectional"))
    )
    (net (code "72") (name "unconnected-(B1-Pad26)") (class "Default")
      (node (ref "B1") (pin "26") (pinfunction "26_26") (pintype "bidirectional"))
    )
    (net (code "73") (name "unconnected-(B1-Pad28)") (class "Default")
      (node (ref "B1") (pin "28") (pinfunction "28_28") (pintype "bidirectional"))
    )
    (net (code "74") (name "unconnected-(B1-Pad30)") (class "Default")
      (node (ref "B1") (pin "30") (pinfunction "30_30") (pintype "bidirectional"))
    )
    (net (code "75") (name "unconnected-(B1-Pad31)") (class "Default")
      (node (ref "B1") (pin "31") (pinfunction "31_31") (pintype "bidirectional"))
    )
    (net (code "76") (name "unconnected-(B1-Pad32)") (class "Default")
      (node (ref "B1") (pin "32") (pinfunction "32_32") (pintype "bidirectional"))
    )
    (net (code "77") (name "unconnected-(B1-Pad33)") (class "Default")
      (node (ref "B1") (pin "33") (pinfunction "33_33") (pintype "bidirectional"))
    )
    (net (code "78") (name "unconnected-(B1-Pad34)") (class "Default")
      (node (ref "B1") (pin "34") (pinfunction "34_34") (pintype "bidirectional"))
    )
    (net (code "79") (name "unconnected-(B1-Pad35)") (class "Default")
      (node (ref "B1") (pin "35") (pinfunction "35_35") (pintype "bidirectional"))
    )
    (net (code "80") (name "unconnected-(B1-Pad36)") (class "Default")
      (node (ref "B1") (pin "36") (pinfunction "36_36") (pintype "bidirectional"))
    )
    (net (code "81") (name "unconnected-(B1-Pad37)") (class "Default")
      (node (ref "B1") (pin "37") (pinfunction "37_37") (pintype "bidirectional"))
    )
    (net (code "82") (name "unconnected-(B1-Pad38)") (class "Default")
      (node (ref "B1") (pin "38") (pinfunction "38_38") (pintype "bidirectional"))
    )
    (net (code "83") (name "unconnected-(B1-Pad39)") (class "Default")
      (node (ref "B1") (pin "39") (pinfunction "39_39") (pintype "bidirectional"))
    )
    (net (code "84") (name "unconnected-(B1-Pad40)") (class "Default")
      (node (ref "B1") (pin "40") (pinfunction "40_40") (pintype "bidirectional"))
    )
    (net (code "85") (name "unconnected-(B1-Pad41)") (class "Default")
      (node (ref "B1") (pin "41") (pinfunction "41_41") (pintype "bidirectional"))
    )
    (net (code "86") (name "unconnected-(B1-Pad42)") (class "Default")
      (node (ref "B1") (pin "42") (pinfunction "42_42") (pintype "bidirectional"))
    )
    (net (code "87") (name "unconnected-(B1-Pad43)") (class "Default")
      (node (ref "B1") (pin "43") (pinfunction "43_43") (pintype "bidirectional"))
    )
    (net (code "88") (name "unconnected-(B1-Pad44)") (class "Default")
      (node (ref "B1") (pin "44") (pinfunction "44_44") (pintype "bidirectional"))
    )
    (net (code "89") (name "unconnected-(B1-Pad45)") (class "Default")
      (node (ref "B1") (pin "45") (pinfunction "45_45") (pintype "bidirectional"))
    )
    (net (code "90") (name "unconnected-(B1-Pad46)") (class "Default")
      (node (ref "B1") (pin "46") (pinfunction "46_46") (pintype "bidirectional"))
    )
    (net (code "91") (name "unconnected-(B1-Pad47)") (class "Default")
      (node (ref "B1") (pin "47") (pinfunction "47_47") (pintype "bidirectional"))
    )
    (net (code "92") (name "unconnected-(B1-Pad48)") (class "Default")
      (node (ref "B1") (pin "48") (pinfunction "48_48") (pintype "bidirectional"))
    )
    (net (code "93") (name "unconnected-(B1-Pad49)") (class "Default")
      (node (ref "B1") (pin "49") (pinfunction "49_49") (pintype "bidirectional"))
    )
    (net (code "94") (name "unconnected-(B1-Pad50)") (class "Default")
      (node (ref "B1") (pin "50") (pinfunction "50_50") (pintype "bidirectional"))
    )
    (net (code "95") (name "unconnected-(B1-Pad51)") (class "Default")
      (node (ref "B1") (pin "51") (pinfunction "51_51") (pintype "bidirectional"))
    )
    (net (code "96") (name "unconnected-(B1-Pad52)") (class "Default")
      (node (ref "B1") (pin "52") (pinfunction "52_52") (pintype "bidirectional"))
    )
    (net (code "97") (name "unconnected-(B1-Pad53)") (class "Default")
      (node (ref "B1") (pin "53") (pinfunction "53_53") (pintype "bidirectional"))
    )
    (net (code "98") (name "unconnected-(B1-PadAREF)") (class "Default")
      (node (ref "B1") (pin "AREF") (pinfunction "AREF_AREF") (pintype "bidirectional"))
    )
    (net (code "99") (name "unconnected-(B1-PadRESET)") (class "Default")
      (node (ref "B1") (pin "RESET") (pinfunction "RESET_RESET") (pintype "bidirectional"))
    )
    (net (code "100") (name "unconnected-(U$2-A0-PadJP1.2)") (class "Default")
      (node (ref "U$2") (pin "JP1.2") (pinfunction "A0_JP1.2") (pintype "bidirectional"))
    )
    (net (code "101") (name "unconnected-(U$2-D0-PadJP1.3)") (class "Default")
      (node (ref "U$2") (pin "JP1.3") (pinfunction "D0_JP1.3") (pintype "bidirectional"))
    )
    (net (code "102") (name "unconnected-(U$2-D1-PadJP2.3)") (class "Default")
      (node (ref "U$2") (pin "JP2.3") (pinfunction "D1_JP2.3") (pintype "bidirectional"))
    )
    (net (code "103") (name "unconnected-(U$2-D2-PadJP2.4)") (class "Default")
      (node (ref "U$2") (pin "JP2.4") (pinfunction "D2_JP2.4") (pintype "bidirectional"))
    )
    (net (code "104") (name "unconnected-(U$2-D3-PadJP2.5)") (class "Default")
      (node (ref "U$2") (pin "JP2.5") (pinfunction "D3_JP2.5") (pintype "bidirectional"))
    )
    (net (code "105") (name "unconnected-(U$2-D4-PadJP2.6)") (class "Default")
      (node (ref "U$2") (pin "JP2.6") (pinfunction "D4_JP2.6") (pintype "bidirectional"))
    )
    (net (code "106") (name "unconnected-(U$2-D5-PadJP1.4)") (class "Default")
      (node (ref "U$2") (pin "JP1.4") (pinfunction "D5_JP1.4") (pintype "bidirectional"))
    )
    (net (code "107") (name "unconnected-(U$2-D6-PadJP1.5)") (class "Default")
      (node (ref "U$2") (pin "JP1.5") (pinfunction "D6_JP1.5") (pintype "bidirectional"))
    )
    (net (code "108") (name "unconnected-(U$2-D7-PadJP1.6)") (class "Default")
      (node (ref "U$2") (pin "JP1.6") (pinfunction "D7_JP1.6") (pintype "bidirectional"))
    )
    (net (code "109") (name "unconnected-(U$2-D8-PadJP1.7)") (class "Default")
      (node (ref "U$2") (pin "JP1.7") (pinfunction "D8_JP1.7") (pintype "bidirectional"))
    )
    (net (code "110") (name "unconnected-(U$2-RST-PadJP1.1)") (class "Default")
      (node (ref "U$2") (pin "JP1.1") (pinfunction "RST_JP1.1") (pintype "bidirectional"))
    )
    (net (code "111") (name "unconnected-(U$3-32K-PadJ1.1)") (class "Default")
      (node (ref "U$3") (pin "J1.1") (pinfunction "32K_J1.1") (pintype "bidirectional"))
    )
    (net (code "112") (name "unconnected-(U$3-SCL.2-PadJ2.1)") (class "Default")
      (node (ref "U$3") (pin "J2.1") (pinfunction "SCL.2_J2.1") (pintype "bidirectional"))
    )
    (net (code "113") (name "unconnected-(U$3-SDA.2-PadJ2.2)") (class "Default")
      (node (ref "U$3") (pin "J2.2") (pinfunction "SDA.2_J2.2") (pintype "bidirectional"))
    )
    (net (code "114") (name "unconnected-(U$3-SQW-PadJ1.2)") (class "Default")
      (node (ref "U$3") (pin "J1.2") (pinfunction "SQW_J1.2") (pintype "bidirectional"))
    )
  )
)
